# Beacon.net
KiCad netlist of a schematic drawn in Altium Designer
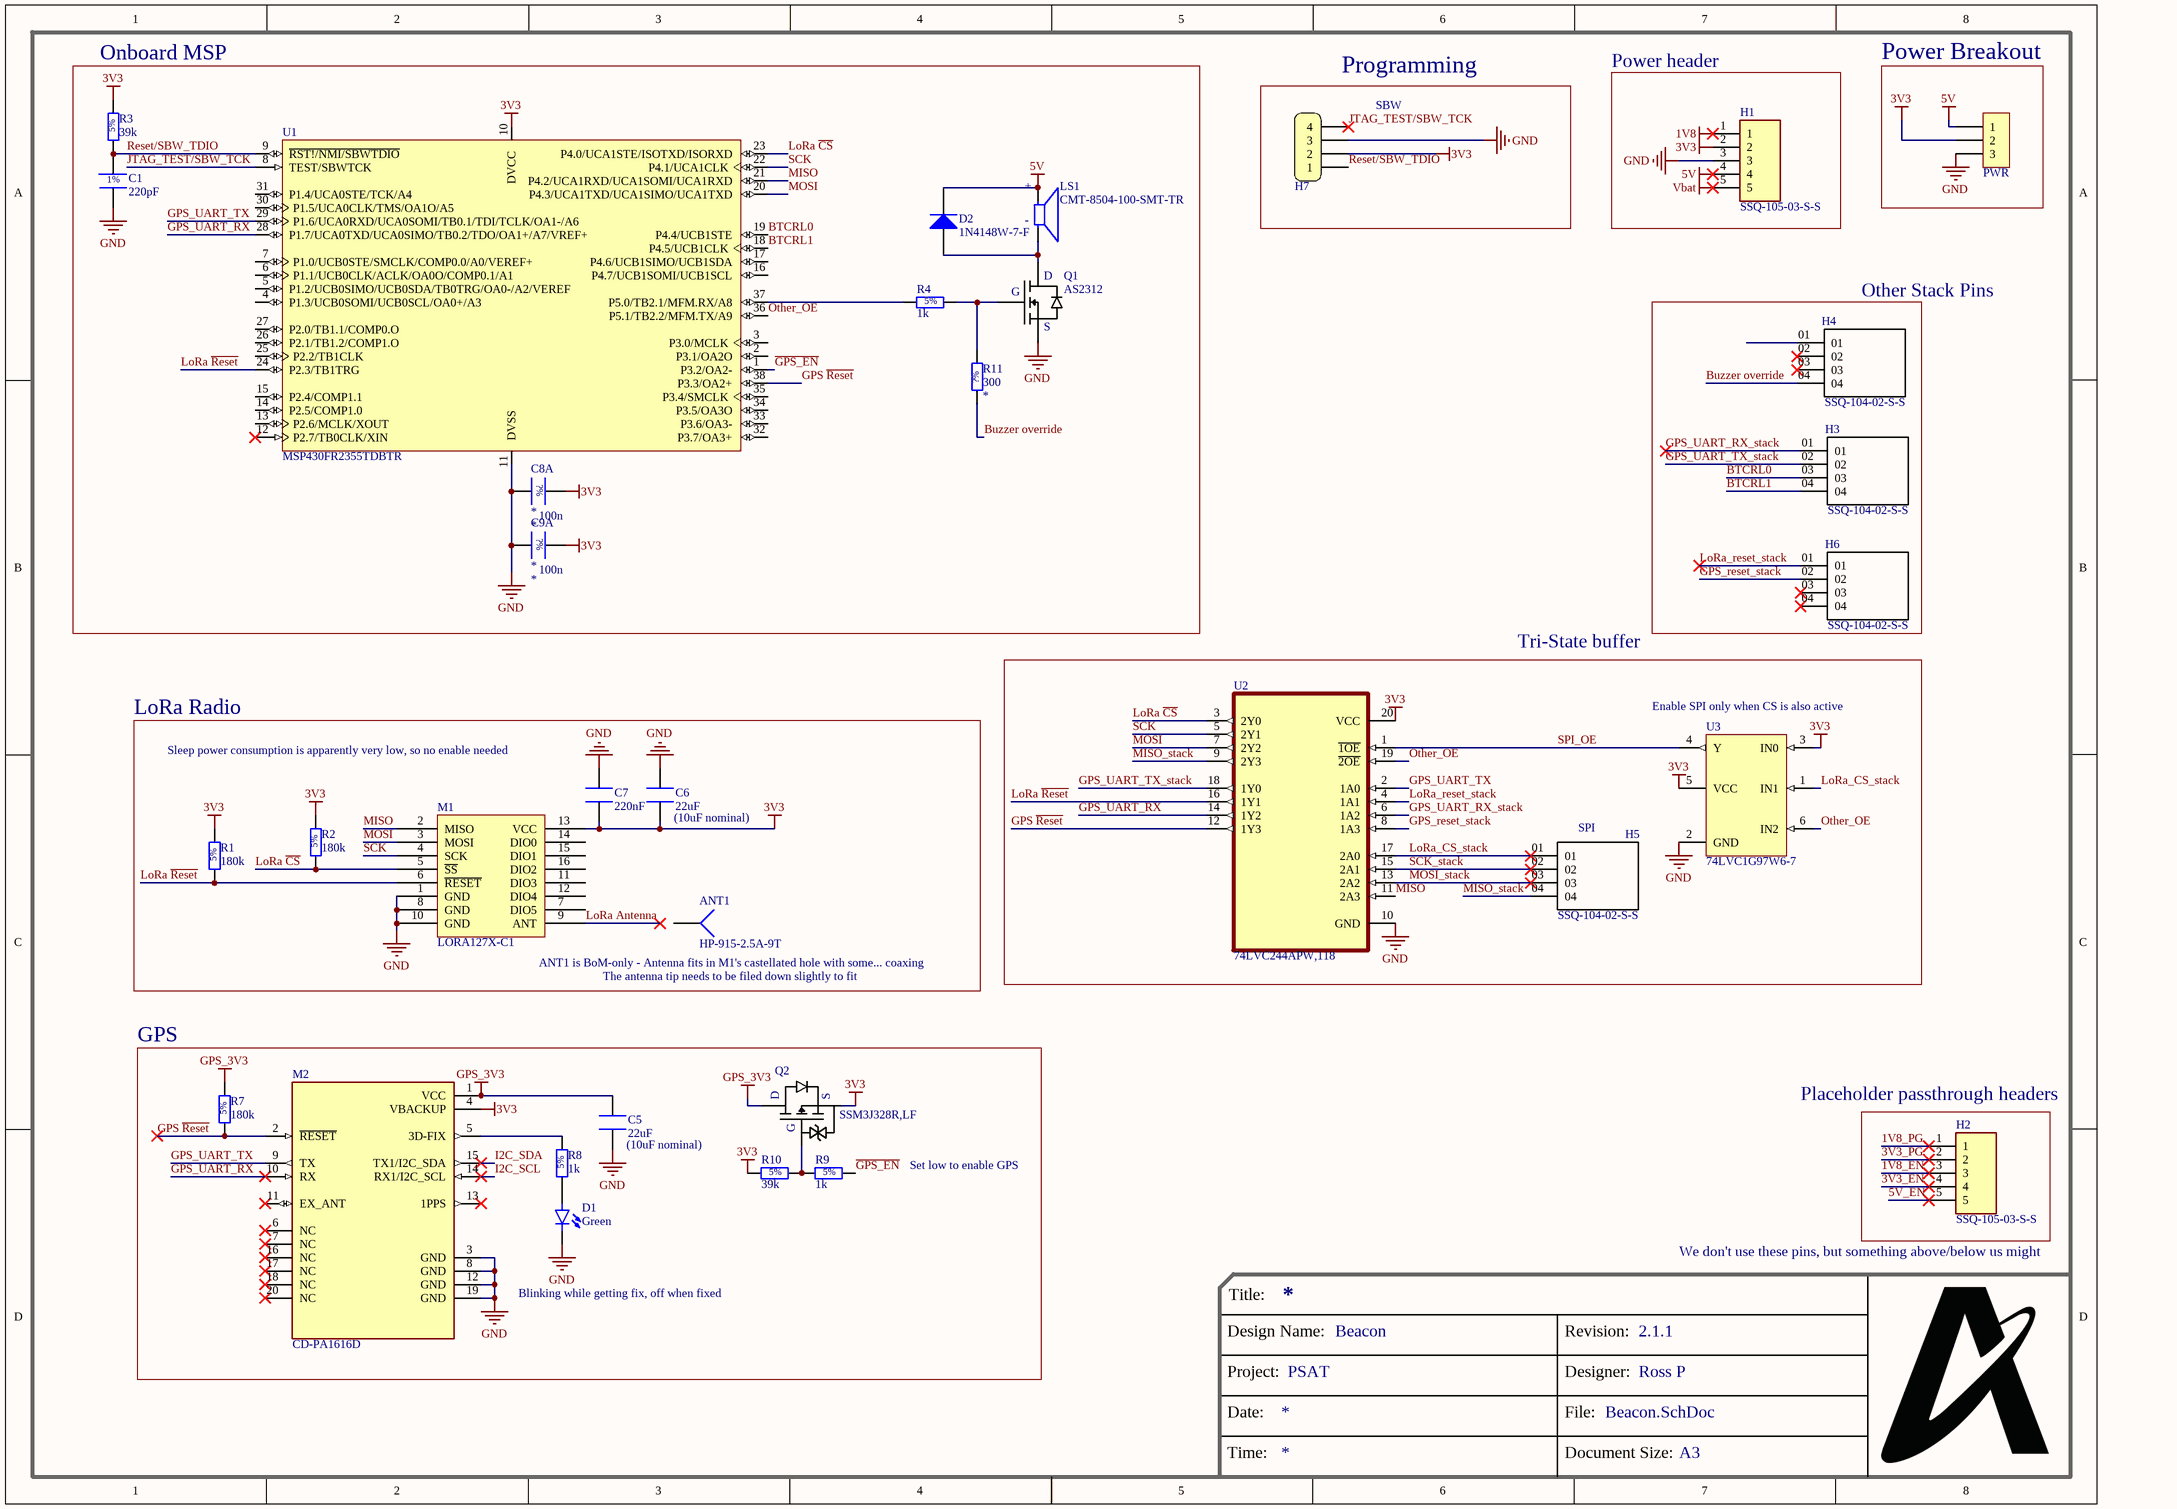
[diagram p0: Beacon.SchDoc]

(export (version "E")
  (design (tool "Eeschema 10.0.6"))
  (components
    (comp (ref "ANT1")
      (value "HP-915-2.5A-9T")
      (description "Spring Antenna")
      (libsource (lib "Miscellaneous Connectors") (part "Socket"))
    )
    (comp (ref "C1")
      (value "220pF")
      (footprint "APSS Prototype Parts:CAPACITOR_0805_2012M-70N")
      (description "Passive - Capacitor Series, C0G, 5pF ~ 22nF, 50V, 0805 (2012 Metric), ±1%, -55°C ~ 125°C")
      (fields (field (name "TOLERANCE") "±1%") (field (name "APSS STANDARD PART") "APSS Standard"))
      (libsource (lib "APSS Prototype Parts") (part "GCM2165CxxxxxF Series"))
    )
    (comp (ref "C5")
      (value "22uF")
      (footprint "APSS Prototype Parts:CAPACITOR_0805_2012M-70N")
      (description "Passive - Capacitor, X5R, 22uF Max, 6.3V, 0805 (2012 Metric), ±20%, -55°C ~ 85°C. 8.8uF @ 5V")
      (fields (field (name "TOLERANCE") "±20%") (field (name "MF PART NO.") "C0805C226M9PACTU"))
      (libsource (lib "APSS Prototype Parts") (part "C0805C226M9PACTU"))
    )
    (comp (ref "C6")
      (value "22uF")
      (footprint "APSS Prototype Parts:CAPACITOR_0805_2012M-70N")
      (description "Passive - Capacitor, X5R, 22uF Max, 6.3V, 0805 (2012 Metric), ±20%, -55°C ~ 85°C. 8.8uF @ 5V")
      (fields (field (name "TOLERANCE") "±20%") (field (name "MF PART NO.") "C0805C226M9PACTU"))
      (libsource (lib "APSS Prototype Parts") (part "C0805C226M9PACTU"))
    )
    (comp (ref "C7")
      (value "220nF")
      (footprint "APSS Prototype Parts:CAPACITOR_0805_2012M-70N")
      (fields
        (field (name "TOLERANCE") "±10%")
        (field (name "MF PART NO.") "C0805C224K1RAC7800")
        (field (name "APSS STANDARD PART") "APSS Standard")
      )
      (libsource (lib "APSS Prototype Parts") (part "C0805C224K1RAC7800"))
    )
    (comp (ref "C8")
      (value "100n")
      (footprint "CAPACITOR_0805_2012M-70N")
      (description "Passive - Capacitor, Generic")
      (fields
        (field (name "TOLERANCE") "?%")
        (field (name "MF PART NO.") "*")
        (field (name "ALTIUM_VALUE") "*")
      )
      (libsource (lib "APSS Generic Components") (part "Generic Capacitor"))
    )
    (comp (ref "C9")
      (value "100n")
      (footprint "CAPACITOR_0805_2012M-70N")
      (description "Passive - Capacitor, Generic")
      (fields
        (field (name "TOLERANCE") "?%")
        (field (name "MF PART NO.") "*")
        (field (name "ALTIUM_VALUE") "*")
      )
      (libsource (lib "APSS Generic Components") (part "Generic Capacitor"))
    )
    (comp (ref "D1")
      (value "LTST-C190 Series")
      (footprint "APSS Prototype Parts:LED_0603_1608M_0.80mm")
      (description "Diode - LED, 0603")
      (fields
        (field (name "MF PART NO.") "LTST-C190KGKT")
        (field (name "COLOUR") "Green")
        (field (name "APSS STANDARD PART") "APSS Standard")
      )
      (libsource (lib "APSS Prototype Parts") (part "LTST-C190 Series"))
    )
    (comp (ref "D2")
      (value "1N4148W-7-F")
      (footprint "SOD123")
      (description "DIODE GEN PURP 100V 300MA SOD123")
      (fields
        (field (name "MANUFACTURER") "Diodes Incorporated")
        (field (name "MANUFACTURER PART NUMBER") "1N4148W-13-F")
      )
      (libsource (lib "EE209_Library") (part "1N4148_SMT_SOD123"))
    )
    (comp (ref "H1")
      (value "SSQ-105-03-S-S")
      (footprint "SAMTEC_SSQ-105-03-S-S:SAMTEC_SSQ-105-03-S-S")
      (libsource (lib "SSQ-105-03-S-S") (part "SSQ-105-03-S-S"))
    )
    (comp (ref "H2")
      (value "SSQ-105-03-S-S")
      (footprint "SAMTEC_SSQ-105-03-S-S:SAMTEC_SSQ-105-03-S-S")
      (libsource (lib "SSQ-105-03-S-S") (part "SSQ-105-03-S-S"))
    )
    (comp (ref "H3")
      (value "SSQ-104-02-S-S")
      (footprint "*SAMTEC_SSQ-104-02-S-S_SSQ-104-02-S-S(Primary)")
      (libsource (lib "SSQ-104-02-S-S") (part "SSQ-104-02-S-S"))
    )
    (comp (ref "H4")
      (value "SSQ-104-02-S-S")
      (footprint "*SAMTEC_SSQ-104-02-S-S_SSQ-104-02-S-S(Primary)")
      (libsource (lib "SSQ-104-02-S-S") (part "SSQ-104-02-S-S"))
    )
    (comp (ref "H5")
      (value "SSQ-104-02-S-S")
      (footprint "*SAMTEC_SSQ-104-02-S-S_SSQ-104-02-S-S(Primary)")
      (libsource (lib "SSQ-104-02-S-S") (part "SSQ-104-02-S-S"))
    )
    (comp (ref "H6")
      (value "SSQ-104-02-S-S")
      (footprint "*SAMTEC_SSQ-104-02-S-S_SSQ-104-02-S-S(Primary)")
      (libsource (lib "SSQ-104-02-S-S") (part "SSQ-104-02-S-S"))
    )
    (comp (ref "H7")
      (value "Headerless Pogo Holes 4-pin")
      (footprint "APSS Generic Components:POGO_4_PIN_HEADER")
      (libsource (lib "APSS Generic Components") (part "Headerless Pogo Holes 4-pin"))
    )
    (comp (ref "LS1")
      (value "CMT-8504-100-SMT-TR")
      (footprint "XDCR_CMT-8504-100-SMT-TR")
      (description "8.5 mm, 5 Vo-p, 100 dB, Surface Mount (SMT), Magnetic Audio Transducer Buzzer")
      (libsource (lib "CMT-8504-100-SMT-TR") (part "CMT-8504-100-SMT-TR"))
    )
    (comp (ref "M1")
      (value "LORA127X-C1")
      (footprint "LoRa127X-C1")
      (description "LoRa transceiver")
      (libsource (lib "LORA127X-C1") (part "LORA127X-C1"))
    )
    (comp (ref "M2")
      (value "CD-PA1616D")
      (footprint "XCVR_CD-PA1616D")
      (description "CD-PA1616D GNSS patch antenna module")
      (libsource (lib "CD-PA1616D") (part "CD-PA1616D"))
    )
    (comp (ref "PWR")
      (value "HDR,2.54mm,1x3")
      (footprint "APSS Connectors:HEADER_2.54MM_1x3PIN")
      (description "Connector - 2.54mm, 1x3-pin")
      (libsource (lib "APSS Connectors") (part "HDR,2.54mm,1x3"))
    )
    (comp (ref "Q1")
      (value "AS2312")
      (footprint "APSS Prototype Parts:SOT23-3N-1.15mm")
      (description "Transistor - MOSFET, N-Channel AS2312")
      (fields (field (name "POWER") "1.2W") (field (name "APSS STANDARD PART") "APSS Standard"))
      (libsource (lib "APSS Prototype Parts") (part "AS2312"))
    )
    (comp (ref "Q2")
      (value "SSM3J328R,LF")
      (footprint "APSS Prototype Parts:SOT23F-3-0.8mm")
      (description "Transistor - MOSFET, P-Channel SSM3J328R,LF")
      (fields (field (name "POWER") "1W") (field (name "APSS STANDARD PART") "APSS Standard"))
      (libsource (lib "APSS Prototype Parts") (part "SSM3J328R,LF"))
    )
    (comp (ref "R1")
      (value "180k")
      (footprint "APSS Prototype Parts:Resistor_0805_2012M-50N")
      (fields
        (field (name "TOLERANCE") "5%")
        (field (name "POWER") "1/8W")
        (field (name "MF PART NO.") "RMCF0805JT180K")
      )
      (libsource (lib "") (part "RMCF0805JT Series_1"))
    )
    (comp (ref "R2")
      (value "180k")
      (footprint "APSS Prototype Parts:Resistor_0805_2012M-50N")
      (fields
        (field (name "TOLERANCE") "5%")
        (field (name "POWER") "1/8W")
        (field (name "MF PART NO.") "RMCF0805JT180K")
      )
      (libsource (lib "") (part "RMCF0805JT Series_1"))
    )
    (comp (ref "R3")
      (value "39k")
      (footprint "APSS Prototype Parts:Resistor_0805_2012M-50N")
      (fields
        (field (name "TOLERANCE") "5%")
        (field (name "POWER") "1/8W")
        (field (name "MF PART NO.") "RMCF0805JT39K0")
      )
      (libsource (lib "") (part "RMCF0805JT Series_1"))
    )
    (comp (ref "R4")
      (value "1k")
      (footprint "APSS Prototype Parts:Resistor_0805_2012M-50N")
      (fields
        (field (name "TOLERANCE") "5%")
        (field (name "POWER") "1/8W")
        (field (name "MF PART NO.") "RMCF0805JT1K00")
      )
      (libsource (lib "APSS Prototype Parts") (part "RMCF0805JT Series"))
    )
    (comp (ref "R7")
      (value "180k")
      (footprint "APSS Prototype Parts:Resistor_0805_2012M-50N")
      (fields
        (field (name "TOLERANCE") "5%")
        (field (name "POWER") "1/8W")
        (field (name "MF PART NO.") "RMCF0805JT180K")
      )
      (libsource (lib "") (part "RMCF0805JT Series_1"))
    )
    (comp (ref "R8")
      (value "1k")
      (footprint "APSS Prototype Parts:Resistor_0805_2012M-50N")
      (fields
        (field (name "TOLERANCE") "5%")
        (field (name "POWER") "1/8W")
        (field (name "MF PART NO.") "RMCF0805JT1K00")
      )
      (libsource (lib "") (part "RMCF0805JT Series_1"))
    )
    (comp (ref "R9")
      (value "1k")
      (footprint "APSS Prototype Parts:Resistor_0805_2012M-50N")
      (fields
        (field (name "TOLERANCE") "5%")
        (field (name "POWER") "1/8W")
        (field (name "MF PART NO.") "RMCF0805JT1K00")
      )
      (libsource (lib "APSS Prototype Parts") (part "RMCF0805JT Series"))
    )
    (comp (ref "R10")
      (value "39k")
      (footprint "APSS Prototype Parts:Resistor_0805_2012M-50N")
      (fields
        (field (name "TOLERANCE") "5%")
        (field (name "POWER") "1/8W")
        (field (name "MF PART NO.") "RMCF0805JT39K0")
      )
      (libsource (lib "APSS Prototype Parts") (part "RMCF0805JT Series"))
    )
    (comp (ref "R11")
      (value "300")
      (footprint "RESISTOR_0805_2012M-50N")
      (description "Passive - Resistor, Generic")
      (fields (field (name "TOLERANCE") "?%") (field (name "MF PART NO.") "*"))
      (libsource (lib "APSS Generic Components") (part "Generic Resistor"))
    )
    (comp (ref "U1")
      (value "MSP430FR2355TDBTR")
      (footprint "APSS Prototype Parts:TSSOP65P640X120-0.5mm-38N")
      (fields
        (field (name "MF PART NO.") "MSP430FR2355TPT")
        (field (name "APSS STANDARD PART") "APSS Standard")
      )
      (libsource (lib "APSS Prototype Parts") (part "MSP430FR2355TDBTR"))
    )
    (comp (ref "U2")
      (value "74LVC244APW,118")
      (footprint "SOP65P640X110-20N:SOP65P640X110-20N")
      (description "Octal buffer/line driver")
      (fields (field (name "MP") "74LVC244APW-118"))
      (libsource (lib "74LVC244APW,118") (part "74LVC244APW,118"))
    )
    (comp (ref "U3")
      (value "74LVC1G97W6-7")
      (footprint "APSS Prototype Parts:SOT23-6N-1.4mm")
      (description "IC - Multifunction Logic Gate, 1 Circuit, 3 Input, 1.65 - 5.5V, AND, OR, NOT, MUX, SOT-23-6")
      (fields (field (name "APSS STANDARD PART") "APSS Standard"))
      (libsource (lib "APSS Prototype Parts") (part "74LVC1G97W6-7"))
    )
  )
  (nets
    (net (code "1") (name "/1V8_EN") (class "Default")
      (node (ref "H2") (pin "3") (pinfunction "3_3") (pintype "passive+no_connect"))
    )
    (net (code "2") (name "/1V8_PG") (class "Default")
      (node (ref "H2") (pin "1") (pinfunction "1_1") (pintype "passive+no_connect"))
    )
    (net (code "3") (name "/3V3_EN") (class "Default")
      (node (ref "H2") (pin "4") (pinfunction "4_4") (pintype "passive+no_connect"))
    )
    (net (code "4") (name "/3V3_PG") (class "Default")
      (node (ref "H2") (pin "2") (pinfunction "2_2") (pintype "passive+no_connect"))
    )
    (net (code "5") (name "/5V_EN") (class "Default")
      (node (ref "H2") (pin "5") (pinfunction "5_5") (pintype "passive+no_connect"))
    )
    (net (code "7") (name "/BTCRL0") (class "Default")
      (node (ref "H3") (pin "03") (pinfunction "03_03") (pintype "passive"))
      (node (ref "U1") (pin "19") (pinfunction "P4.4/UCB1STE_19") (pintype "bidirectional"))
    )
    (net (code "8") (name "/BTCRL1") (class "Default")
      (node (ref "H3") (pin "04") (pinfunction "04_04") (pintype "passive"))
      (node (ref "U1") (pin "18") (pinfunction "P4.5/UCB1CLK_18") (pintype "bidirectional"))
    )
    (net (code "9") (name "/Buzzer override") (class "Default")
      (node (ref "H4") (pin "04") (pinfunction "04_04") (pintype "passive"))
      (node (ref "R11") (pin "1") (pinfunction "1_1") (pintype "passive"))
    )
    (net (code "10") (name "/GPS ~{Reset}") (class "Default")
      (node (ref "M2") (pin "2") (pinfunction "~{RESET}_2") (pintype "input"))
      (node (ref "R7") (pin "1") (pinfunction "1_1") (pintype "passive"))
      (node (ref "U1") (pin "38") (pinfunction "P3.3/OA2+_38") (pintype "bidirectional"))
      (node (ref "U2") (pin "12") (pinfunction "1Y3_12") (pintype "output"))
    )
    (net (code "11") (name "/GPS_UART_RX") (class "Default")
      (node (ref "M2") (pin "10") (pinfunction "RX_10") (pintype "input"))
      (node (ref "U1") (pin "28") (pinfunction "P1.7/UCA0TXD/UCA0SIMO/TB0.2/TDO/OA1+/A7/VREF+_28") (pintype "bidirectional"))
      (node (ref "U2") (pin "14") (pinfunction "1Y2_14") (pintype "output"))
    )
    (net (code "12") (name "/GPS_UART_RX_stack") (class "Default")
      (node (ref "H3") (pin "01") (pinfunction "01_01") (pintype "passive"))
      (node (ref "U2") (pin "6") (pinfunction "1A2_6") (pintype "input"))
    )
    (net (code "13") (name "/GPS_UART_TX") (class "Default")
      (node (ref "M2") (pin "9") (pinfunction "TX_9") (pintype "output"))
      (node (ref "U1") (pin "29") (pinfunction "P1.6/UCA0RXD/UCA0SOMI/TB0.1/TDI/TCLK/OA1-/A6_29") (pintype "bidirectional"))
      (node (ref "U2") (pin "2") (pinfunction "1A0_2") (pintype "input"))
    )
    (net (code "14") (name "/GPS_UART_TX_stack") (class "Default")
      (node (ref "H3") (pin "02") (pinfunction "02_02") (pintype "passive"))
      (node (ref "U2") (pin "18") (pinfunction "1Y0_18") (pintype "output"))
    )
    (net (code "15") (name "/GPS_reset_stack") (class "Default")
      (node (ref "H6") (pin "02") (pinfunction "02_02") (pintype "passive"))
      (node (ref "U2") (pin "8") (pinfunction "1A3_8") (pintype "input"))
    )
    (net (code "16") (name "/I2C_SCL") (class "Default")
      (node (ref "M2") (pin "14") (pinfunction "RX1/I2C_SCL_14") (pintype "input+no_connect"))
    )
    (net (code "17") (name "/I2C_SDA") (class "Default")
      (node (ref "M2") (pin "15") (pinfunction "TX1/I2C_SDA_15") (pintype "output+no_connect"))
    )
    (net (code "18") (name "/JTAG_TEST{slash}SBW_TCK") (class "Default")
      (node (ref "H7") (pin "4") (pinfunction "4_4") (pintype "passive"))
      (node (ref "U1") (pin "8") (pinfunction "TEST/SBWTCK_8") (pintype "input"))
    )
    (net (code "19") (name "/LoRa Antenna") (class "Default")
      (node (ref "M1") (pin "9") (pinfunction "ANT_9") (pintype "passive+no_connect"))
    )
    (net (code "20") (name "/LoRa ~{CS}") (class "Default")
      (node (ref "M1") (pin "5") (pinfunction "~{SS}_5") (pintype "passive"))
      (node (ref "R2") (pin "1") (pinfunction "1_1") (pintype "passive"))
      (node (ref "U1") (pin "23") (pinfunction "P4.0/UCA1STE/ISOTXD/ISORXD_23") (pintype "bidirectional"))
      (node (ref "U2") (pin "3") (pinfunction "2Y0_3") (pintype "output"))
    )
    (net (code "21") (name "/LoRa ~{Reset}") (class "Default")
      (node (ref "M1") (pin "6") (pinfunction "~{RESET}_6") (pintype "passive"))
      (node (ref "R1") (pin "1") (pinfunction "1_1") (pintype "passive"))
      (node (ref "U1") (pin "24") (pinfunction "P2.3/TB1TRG_24") (pintype "bidirectional"))
      (node (ref "U2") (pin "16") (pinfunction "1Y1_16") (pintype "output"))
    )
    (net (code "22") (name "/LoRa_CS_stack") (class "Default")
      (node (ref "H5") (pin "01") (pinfunction "01_01") (pintype "passive"))
      (node (ref "U2") (pin "17") (pinfunction "2A0_17") (pintype "input"))
      (node (ref "U3") (pin "1") (pinfunction "IN1_1") (pintype "input"))
    )
    (net (code "23") (name "/LoRa_reset_stack") (class "Default")
      (node (ref "H6") (pin "01") (pinfunction "01_01") (pintype "passive"))
      (node (ref "U2") (pin "4") (pinfunction "1A1_4") (pintype "input"))
    )
    (net (code "24") (name "/MISO") (class "Default")
      (node (ref "M1") (pin "2") (pinfunction "MISO_2") (pintype "passive"))
      (node (ref "U1") (pin "21") (pinfunction "P4.2/UCA1RXD/UCA1SOMI/UCA1RXD_21") (pintype "bidirectional"))
      (node (ref "U2") (pin "11") (pinfunction "2A3_11") (pintype "input"))
    )
    (net (code "25") (name "/MISO_stack") (class "Default")
      (node (ref "H5") (pin "04") (pinfunction "04_04") (pintype "passive"))
      (node (ref "U2") (pin "9") (pinfunction "2Y3_9") (pintype "output"))
    )
    (net (code "26") (name "/MOSI") (class "Default")
      (node (ref "M1") (pin "3") (pinfunction "MOSI_3") (pintype "passive"))
      (node (ref "U1") (pin "20") (pinfunction "P4.3/UCA1TXD/UCA1SIMO/UCA1TXD_20") (pintype "bidirectional"))
      (node (ref "U2") (pin "7") (pinfunction "2Y2_7") (pintype "output"))
    )
    (net (code "27") (name "/MOSI_stack") (class "Default")
      (node (ref "H5") (pin "03") (pinfunction "03_03") (pintype "passive"))
      (node (ref "U2") (pin "13") (pinfunction "2A2_13") (pintype "input"))
    )
    (net (code "28") (name "/Other_OE") (class "Default")
      (node (ref "U1") (pin "36") (pinfunction "P5.1/TB2.2/MFM.TX/A9_36") (pintype "bidirectional"))
      (node (ref "U2") (pin "19") (pinfunction "~{2OE}_19") (pintype "input"))
      (node (ref "U3") (pin "6") (pinfunction "IN2_6") (pintype "input"))
    )
    (net (code "29") (name "/Reset{slash}SBW_TDIO") (class "Default")
      (node (ref "C1") (pin "2") (pinfunction "2_2") (pintype "passive"))
      (node (ref "H7") (pin "1") (pinfunction "1_1") (pintype "passive"))
      (node (ref "R3") (pin "1") (pinfunction "1_1") (pintype "passive"))
      (node (ref "U1") (pin "9") (pinfunction "~{RST!/NMI/SBWTDIO}_9") (pintype "bidirectional"))
    )
    (net (code "30") (name "/SCK") (class "Default")
      (node (ref "M1") (pin "4") (pinfunction "SCK_4") (pintype "passive"))
      (node (ref "U1") (pin "22") (pinfunction "P4.1/UCA1CLK_22") (pintype "bidirectional"))
      (node (ref "U2") (pin "5") (pinfunction "2Y1_5") (pintype "output"))
    )
    (net (code "31") (name "/SCK_stack") (class "Default")
      (node (ref "H5") (pin "02") (pinfunction "02_02") (pintype "passive"))
      (node (ref "U2") (pin "15") (pinfunction "2A1_15") (pintype "input"))
    )
    (net (code "32") (name "/SPI_OE") (class "Default")
      (node (ref "U2") (pin "1") (pinfunction "~{1OE}_1") (pintype "input"))
      (node (ref "U3") (pin "4") (pinfunction "Y_4") (pintype "output"))
    )
    (net (code "33") (name "/~{GPS_EN}") (class "Default")
      (node (ref "R9") (pin "2") (pinfunction "2_2") (pintype "passive"))
      (node (ref "U1") (pin "1") (pinfunction "P3.2/OA2-_1") (pintype "bidirectional"))
    )
    (net (code "34") (name "1V8") (class "Default")
      (node (ref "H1") (pin "1") (pinfunction "1_1") (pintype "passive"))
    )
    (net (code "35") (name "3V3") (class "Default")
      (node (ref "C6") (pin "1") (pinfunction "1_1") (pintype "passive"))
      (node (ref "C7") (pin "1") (pinfunction "1_1") (pintype "passive"))
      (node (ref "C8") (pin "2") (pinfunction "2_2") (pintype "passive"))
      (node (ref "C9") (pin "2") (pinfunction "2_2") (pintype "passive"))
      (node (ref "H1") (pin "2") (pinfunction "2_2") (pintype "passive"))
      (node (ref "H7") (pin "2") (pinfunction "2_2") (pintype "passive"))
      (node (ref "M1") (pin "13") (pinfunction "VCC_13") (pintype "passive"))
      (node (ref "M2") (pin "4") (pinfunction "VBACKUP_4") (pintype "power_in"))
      (node (ref "PWR") (pin "2") (pinfunction "2_2") (pintype "passive"))
      (node (ref "Q2") (pin "2") (pinfunction "S_2") (pintype "passive"))
      (node (ref "R1") (pin "2") (pinfunction "2_2") (pintype "passive"))
      (node (ref "R10") (pin "1") (pinfunction "1_1") (pintype "passive"))
      (node (ref "R2") (pin "2") (pinfunction "2_2") (pintype "passive"))
      (node (ref "R3") (pin "2") (pinfunction "2_2") (pintype "passive"))
      (node (ref "U1") (pin "10") (pinfunction "DVCC_10") (pintype "power_in"))
      (node (ref "U2") (pin "20") (pinfunction "VCC_20") (pintype "power_in"))
      (node (ref "U3") (pin "3") (pinfunction "IN0_3") (pintype "input"))
      (node (ref "U3") (pin "5") (pinfunction "VCC_5") (pintype "power_in"))
    )
    (net (code "36") (name "5V") (class "Default")
      (node (ref "D2") (pin "2") (pinfunction "K_2") (pintype "passive"))
      (node (ref "H1") (pin "4") (pinfunction "4_4") (pintype "passive"))
      (node (ref "LS1") (pin "P") (pinfunction "P_P") (pintype "passive"))
      (node (ref "PWR") (pin "1") (pinfunction "1_1") (pintype "passive"))
    )
    (net (code "37") (name "GND") (class "Default")
      (node (ref "C1") (pin "1") (pinfunction "1_1") (pintype "passive"))
      (node (ref "C5") (pin "1") (pinfunction "1_1") (pintype "passive"))
      (node (ref "C6") (pin "2") (pinfunction "2_2") (pintype "passive"))
      (node (ref "C7") (pin "2") (pinfunction "2_2") (pintype "passive"))
      (node (ref "C8") (pin "1") (pinfunction "1_1") (pintype "passive"))
      (node (ref "C9") (pin "1") (pinfunction "1_1") (pintype "passive"))
      (node (ref "D1") (pin "C") (pinfunction "C_C") (pintype "passive"))
      (node (ref "H1") (pin "3") (pinfunction "3_3") (pintype "passive"))
      (node (ref "H7") (pin "3") (pinfunction "3_3") (pintype "passive"))
      (node (ref "M1") (pin "1") (pinfunction "GND_1") (pintype "passive"))
      (node (ref "M1") (pin "10") (pinfunction "GND_10") (pintype "passive"))
      (node (ref "M1") (pin "8") (pinfunction "GND_8") (pintype "passive"))
      (node (ref "M2") (pin "12") (pinfunction "GND_12") (pintype "power_in"))
      (node (ref "M2") (pin "19") (pinfunction "GND_19") (pintype "power_in"))
      (node (ref "M2") (pin "3") (pinfunction "GND_3") (pintype "power_in"))
      (node (ref "M2") (pin "8") (pinfunction "GND_8") (pintype "power_in"))
      (node (ref "PWR") (pin "3") (pinfunction "3_3") (pintype "passive"))
      (node (ref "Q1") (pin "2") (pinfunction "S_2") (pintype "passive"))
      (node (ref "U1") (pin "11") (pinfunction "DVSS_11") (pintype "power_in"))
      (node (ref "U2") (pin "10") (pinfunction "GND_10") (pintype "passive"))
      (node (ref "U3") (pin "2") (pinfunction "GND_2") (pintype "passive"))
    )
    (net (code "38") (name "GPS_3V3") (class "Default")
      (node (ref "C5") (pin "2") (pinfunction "2_2") (pintype "passive"))
      (node (ref "M2") (pin "1") (pinfunction "VCC_1") (pintype "power_in"))
      (node (ref "Q2") (pin "3") (pinfunction "D_3") (pintype "passive"))
      (node (ref "R7") (pin "2") (pinfunction "2_2") (pintype "passive"))
    )
    (net (code "39") (name "Net-(D1-PadA)") (class "Default")
      (node (ref "D1") (pin "A") (pinfunction "A_A") (pintype "passive"))
      (node (ref "R8") (pin "1") (pinfunction "1_1") (pintype "passive"))
    )
    (net (code "40") (name "Net-(D2-A)") (class "Default")
      (node (ref "D2") (pin "1") (pinfunction "A_1") (pintype "passive"))
      (node (ref "LS1") (pin "N") (pinfunction "N_N") (pintype "passive"))
      (node (ref "Q1") (pin "3") (pinfunction "D_3") (pintype "passive"))
    )
    (net (code "41") (name "Net-(M2-3D-FIX)") (class "Default")
      (node (ref "M2") (pin "5") (pinfunction "3D-FIX_5") (pintype "output"))
      (node (ref "R8") (pin "2") (pinfunction "2_2") (pintype "passive"))
    )
    (net (code "42") (name "Net-(Q1-G)") (class "Default")
      (node (ref "Q1") (pin "1") (pinfunction "G_1") (pintype "passive"))
      (node (ref "R11") (pin "2") (pinfunction "2_2") (pintype "passive"))
      (node (ref "R4") (pin "2") (pinfunction "2_2") (pintype "passive"))
    )
    (net (code "43") (name "Net-(Q2-G)") (class "Default")
      (node (ref "Q2") (pin "1") (pinfunction "G_1") (pintype "passive"))
      (node (ref "R10") (pin "2") (pinfunction "2_2") (pintype "passive"))
      (node (ref "R9") (pin "1") (pinfunction "1_1") (pintype "passive"))
    )
    (net (code "44") (name "Net-(U1-P5.0{slash}TB2.1{slash}MFM.RX{slash}A8)") (class "Default")
      (node (ref "R4") (pin "1") (pinfunction "1_1") (pintype "passive"))
      (node (ref "U1") (pin "37") (pinfunction "P5.0/TB2.1/MFM.RX/A8_37") (pintype "bidirectional"))
    )
    (net (code "45") (name "Vbat") (class "Default")
      (node (ref "H1") (pin "5") (pinfunction "5_5") (pintype "passive"))
    )
    (net (code "46") (name "unconnected-(ANT1-Pad1)") (class "Default")
      (node (ref "ANT1") (pin "1") (pinfunction "1_1") (pintype "passive"))
    )
    (net (code "47") (name "unconnected-(H4-Pad01)") (class "Default")
      (node (ref "H4") (pin "01") (pinfunction "01_01") (pintype "passive"))
    )
    (net (code "48") (name "unconnected-(H4-Pad02)") (class "Default")
      (node (ref "H4") (pin "02") (pinfunction "02_02") (pintype "passive+no_connect"))
    )
    (net (code "49") (name "unconnected-(H4-Pad03)") (class "Default")
      (node (ref "H4") (pin "03") (pinfunction "03_03") (pintype "passive+no_connect"))
    )
    (net (code "50") (name "unconnected-(H6-Pad03)") (class "Default")
      (node (ref "H6") (pin "03") (pinfunction "03_03") (pintype "passive+no_connect"))
    )
    (net (code "51") (name "unconnected-(H6-Pad04)") (class "Default")
      (node (ref "H6") (pin "04") (pinfunction "04_04") (pintype "passive+no_connect"))
    )
    (net (code "52") (name "unconnected-(M1-DIO0-Pad14)") (class "Default")
      (node (ref "M1") (pin "14") (pinfunction "DIO0_14") (pintype "passive"))
    )
    (net (code "53") (name "unconnected-(M1-DIO1-Pad15)") (class "Default")
      (node (ref "M1") (pin "15") (pinfunction "DIO1_15") (pintype "passive"))
    )
    (net (code "54") (name "unconnected-(M1-DIO2-Pad16)") (class "Default")
      (node (ref "M1") (pin "16") (pinfunction "DIO2_16") (pintype "passive"))
    )
    (net (code "55") (name "unconnected-(M1-DIO3-Pad11)") (class "Default")
      (node (ref "M1") (pin "11") (pinfunction "DIO3_11") (pintype "passive"))
    )
    (net (code "56") (name "unconnected-(M1-DIO4-Pad12)") (class "Default")
      (node (ref "M1") (pin "12") (pinfunction "DIO4_12") (pintype "passive"))
    )
    (net (code "57") (name "unconnected-(M1-DIO5-Pad7)") (class "Default")
      (node (ref "M1") (pin "7") (pinfunction "DIO5_7") (pintype "passive"))
    )
    (net (code "58") (name "unconnected-(M2-1PPS-Pad13)") (class "Default")
      (node (ref "M2") (pin "13") (pinfunction "1PPS_13") (pintype "output+no_connect"))
    )
    (net (code "59") (name "unconnected-(M2-EX_ANT-Pad11)") (class "Default")
      (node (ref "M2") (pin "11") (pinfunction "EX_ANT_11") (pintype "bidirectional+no_connect"))
    )
    (net (code "60") (name "unconnected-(M2-NC-Pad6)") (class "Default")
      (node (ref "M2") (pin "6") (pinfunction "NC_6") (pintype "passive+no_connect"))
    )
    (net (code "61") (name "unconnected-(M2-NC-Pad7)") (class "Default")
      (node (ref "M2") (pin "7") (pinfunction "NC_7") (pintype "passive+no_connect"))
    )
    (net (code "62") (name "unconnected-(M2-NC-Pad16)") (class "Default")
      (node (ref "M2") (pin "16") (pinfunction "NC_16") (pintype "passive+no_connect"))
    )
    (net (code "63") (name "unconnected-(M2-NC-Pad17)") (class "Default")
      (node (ref "M2") (pin "17") (pinfunction "NC_17") (pintype "passive+no_connect"))
    )
    (net (code "64") (name "unconnected-(M2-NC-Pad18)") (class "Default")
      (node (ref "M2") (pin "18") (pinfunction "NC_18") (pintype "passive+no_connect"))
    )
    (net (code "65") (name "unconnected-(M2-NC-Pad20)") (class "Default")
      (node (ref "M2") (pin "20") (pinfunction "NC_20") (pintype "passive+no_connect"))
    )
    (net (code "66") (name "unconnected-(U1-P1.0{slash}UCB0STE{slash}SMCLK{slash}COMP0.0{slash}A0{slash}VEREF+-Pad7)") (class "Default")
      (node (ref "U1") (pin "7") (pinfunction "P1.0/UCB0STE/SMCLK/COMP0.0/A0/VEREF+_7") (pintype "bidirectional"))
    )
    (net (code "67") (name "unconnected-(U1-P1.1{slash}UCB0CLK{slash}ACLK{slash}OA0O{slash}COMP0.1{slash}A1-Pad6)") (class "Default")
      (node (ref "U1") (pin "6") (pinfunction "P1.1/UCB0CLK/ACLK/OA0O/COMP0.1/A1_6") (pintype "bidirectional"))
    )
    (net (code "68") (name "unconnected-(U1-P1.2{slash}UCB0SIMO{slash}UCB0SDA{slash}TB0TRG{slash}OA0-{slash}A2{slash}VEREF-Pad5)") (class "Default")
      (node (ref "U1") (pin "5") (pinfunction "P1.2/UCB0SIMO/UCB0SDA/TB0TRG/OA0-/A2/VEREF_5") (pintype "bidirectional"))
    )
    (net (code "69") (name "unconnected-(U1-P1.3{slash}UCB0SOMI{slash}UCB0SCL{slash}OA0+{slash}A3-Pad4)") (class "Default")
      (node (ref "U1") (pin "4") (pinfunction "P1.3/UCB0SOMI/UCB0SCL/OA0+/A3_4") (pintype "bidirectional"))
    )
    (net (code "70") (name "unconnected-(U1-P1.4{slash}UCA0STE{slash}TCK{slash}A4-Pad31)") (class "Default")
      (node (ref "U1") (pin "31") (pinfunction "P1.4/UCA0STE/TCK/A4_31") (pintype "bidirectional"))
    )
    (net (code "71") (name "unconnected-(U1-P1.5{slash}UCA0CLK{slash}TMS{slash}OA1O{slash}A5-Pad30)") (class "Default")
      (node (ref "U1") (pin "30") (pinfunction "P1.5/UCA0CLK/TMS/OA1O/A5_30") (pintype "bidirectional"))
    )
    (net (code "72") (name "unconnected-(U1-P2.0{slash}TB1.1{slash}COMP0.O-Pad27)") (class "Default")
      (node (ref "U1") (pin "27") (pinfunction "P2.0/TB1.1/COMP0.O_27") (pintype "bidirectional"))
    )
    (net (code "73") (name "unconnected-(U1-P2.1{slash}TB1.2{slash}COMP1.O-Pad26)") (class "Default")
      (node (ref "U1") (pin "26") (pinfunction "P2.1/TB1.2/COMP1.O_26") (pintype "bidirectional"))
    )
    (net (code "74") (name "unconnected-(U1-P2.2{slash}TB1CLK-Pad25)") (class "Default")
      (node (ref "U1") (pin "25") (pinfunction "P2.2/TB1CLK_25") (pintype "bidirectional"))
    )
    (net (code "75") (name "unconnected-(U1-P2.4{slash}COMP1.1-Pad15)") (class "Default")
      (node (ref "U1") (pin "15") (pinfunction "P2.4/COMP1.1_15") (pintype "bidirectional"))
    )
    (net (code "76") (name "unconnected-(U1-P2.5{slash}COMP1.0-Pad14)") (class "Default")
      (node (ref "U1") (pin "14") (pinfunction "P2.5/COMP1.0_14") (pintype "bidirectional"))
    )
    (net (code "77") (name "unconnected-(U1-P2.6{slash}MCLK{slash}XOUT-Pad13)") (class "Default")
      (node (ref "U1") (pin "13") (pinfunction "P2.6/MCLK/XOUT_13") (pintype "bidirectional"))
    )
    (net (code "78") (name "unconnected-(U1-P2.7{slash}TB0CLK{slash}XIN-Pad12)") (class "Default")
      (node (ref "U1") (pin "12") (pinfunction "P2.7/TB0CLK/XIN_12") (pintype "input+no_connect"))
    )
    (net (code "79") (name "unconnected-(U1-P3.0{slash}MCLK-Pad3)") (class "Default")
      (node (ref "U1") (pin "3") (pinfunction "P3.0/MCLK_3") (pintype "bidirectional"))
    )
    (net (code "80") (name "unconnected-(U1-P3.1{slash}OA2O-Pad2)") (class "Default")
      (node (ref "U1") (pin "2") (pinfunction "P3.1/OA2O_2") (pintype "bidirectional"))
    )
    (net (code "81") (name "unconnected-(U1-P3.4{slash}SMCLK-Pad35)") (class "Default")
      (node (ref "U1") (pin "35") (pinfunction "P3.4/SMCLK_35") (pintype "bidirectional"))
    )
    (net (code "82") (name "unconnected-(U1-P3.5{slash}OA3O-Pad34)") (class "Default")
      (node (ref "U1") (pin "34") (pinfunction "P3.5/OA3O_34") (pintype "bidirectional"))
    )
    (net (code "83") (name "unconnected-(U1-P3.6{slash}OA3--Pad33)") (class "Default")
      (node (ref "U1") (pin "33") (pinfunction "P3.6/OA3-_33") (pintype "bidirectional"))
    )
    (net (code "84") (name "unconnected-(U1-P3.7{slash}OA3+-Pad32)") (class "Default")
      (node (ref "U1") (pin "32") (pinfunction "P3.7/OA3+_32") (pintype "bidirectional"))
    )
    (net (code "85") (name "unconnected-(U1-P4.6{slash}UCB1SIMO{slash}UCB1SDA-Pad17)") (class "Default")
      (node (ref "U1") (pin "17") (pinfunction "P4.6/UCB1SIMO/UCB1SDA_17") (pintype "bidirectional"))
    )
    (net (code "86") (name "unconnected-(U1-P4.7{slash}UCB1SOMI{slash}UCB1SCL-Pad16)") (class "Default")
      (node (ref "U1") (pin "16") (pinfunction "P4.7/UCB1SOMI/UCB1SCL_16") (pintype "bidirectional"))
    )
  )
)
